# SMD_VR_2023-05-26.net
KiCad netlist of a schematic drawn in Altium Designer
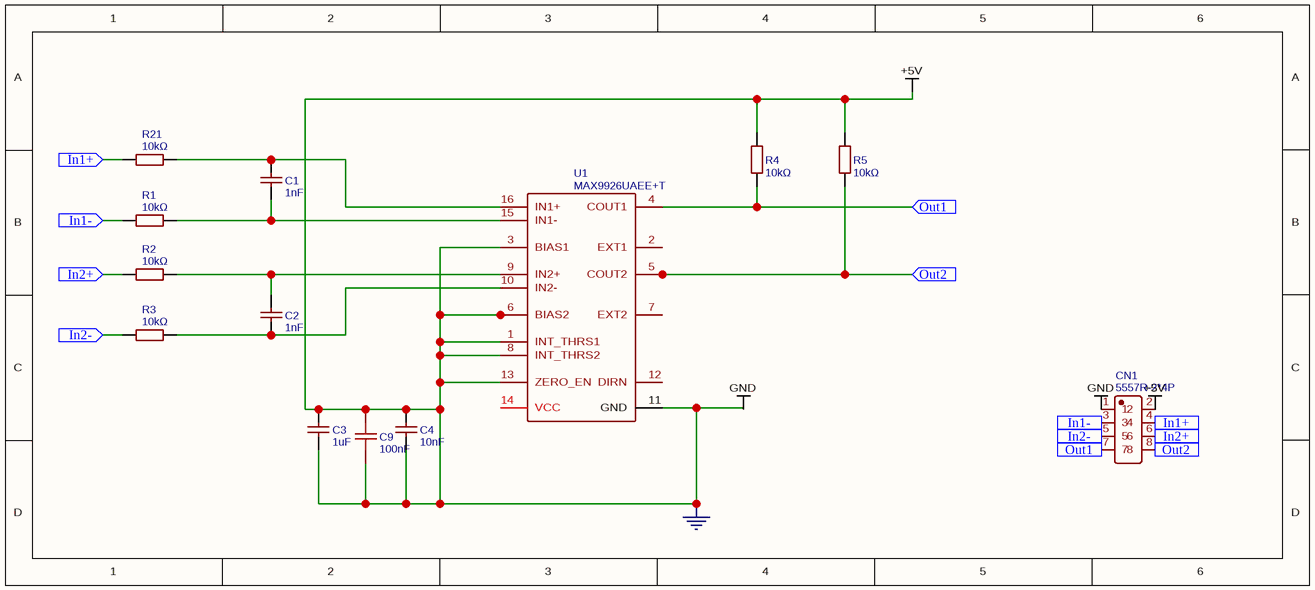
[diagram p0: SMD VR_2023-05-26.schdoc]

(export (version "E")
  (design (tool "Eeschema 10.0.6"))
  (components
    (comp (ref "C1")
      (value "1nF")
      (fields
        (field (name "BOM_MANUFACTURER PART") "CL10B102KB8NNNC")
        (field (name "BOM_SUPPLIER PART") "C1588")
      )
      (libsource (lib "altium-import") (part "root_1_1nF_"))
    )
    (comp (ref "C2")
      (value "1nF")
      (fields
        (field (name "BOM_MANUFACTURER PART") "CL10B102KB8NNNC")
        (field (name "BOM_SUPPLIER PART") "C1588")
      )
      (libsource (lib "altium-import") (part "root_1_1nF_"))
    )
    (comp (ref "C3")
      (value "1uF")
      (fields
        (field (name "BOM_MANUFACTURER PART") "CL10A105KB8NNNC")
        (field (name "BOM_SUPPLIER PART") "C15849")
      )
      (libsource (lib "altium-import") (part "root_1_1uF_"))
    )
    (comp (ref "C4")
      (value "10nF")
      (fields
        (field (name "BOM_MANUFACTURER PART") "CL05B103KB5NNNC")
        (field (name "BOM_SUPPLIER PART") "C15195")
      )
      (libsource (lib "altium-import") (part "root_1_10nF_"))
    )
    (comp (ref "C9")
      (value "100nF")
      (fields
        (field (name "BOM_MANUFACTURER PART") "CC0603KRX7R9BB104")
        (field (name "BOM_SUPPLIER PART") "C14663")
      )
      (libsource (lib "altium-import") (part "root_1_100nF_"))
    )
    (comp (ref "CN1")
      (value "5557R-2*4P")
      (fields (field (name "BOM_SUPPLIER PART") "C477838") (field (name "CONTRIBUTOR") "LCSC"))
      (libsource (lib "altium-import") (part "root_0_5557R-2*4P_"))
    )
    (comp (ref "R1")
      (value "10kΩ")
      (fields
        (field (name "BOM_MANUFACTURER PART") "0402WGF1002TCE")
        (field (name "BOM_SUPPLIER PART") "C25744")
      )
      (libsource (lib "altium-import") (part "root_2_10kΩ_"))
    )
    (comp (ref "R2")
      (value "10kΩ")
      (fields
        (field (name "BOM_MANUFACTURER PART") "0402WGF1002TCE")
        (field (name "BOM_SUPPLIER PART") "C25744")
      )
      (libsource (lib "altium-import") (part "root_2_10kΩ_"))
    )
    (comp (ref "R3")
      (value "10kΩ")
      (fields
        (field (name "BOM_MANUFACTURER PART") "0402WGF1002TCE")
        (field (name "BOM_SUPPLIER PART") "C25744")
      )
      (libsource (lib "altium-import") (part "root_2_10kΩ_"))
    )
    (comp (ref "R4")
      (value "10kΩ")
      (fields
        (field (name "BOM_MANUFACTURER PART") "0402WGF1002TCE")
        (field (name "BOM_SUPPLIER PART") "C25744")
      )
      (libsource (lib "altium-import") (part "root_3_10kΩ_"))
    )
    (comp (ref "R5")
      (value "10kΩ")
      (fields
        (field (name "BOM_MANUFACTURER PART") "0402WGF1002TCE")
        (field (name "BOM_SUPPLIER PART") "C25744")
      )
      (libsource (lib "altium-import") (part "root_3_10kΩ_"))
    )
    (comp (ref "R21")
      (value "10kΩ")
      (fields
        (field (name "BOM_MANUFACTURER PART") "0402WGF1002TCE")
        (field (name "BOM_SUPPLIER PART") "C25744")
      )
      (libsource (lib "altium-import") (part "root_2_10kΩ_"))
    )
    (comp (ref "U1")
      (value "MAX9926UAEE+T")
      (fields (field (name "BOM_MANUFACTURER PART") "?"))
      (libsource (lib "altium-import") (part "root_0_MAX9926UAEE+T_"))
    )
  )
  (nets
    (net (code "1") (name "+5V") (class "Default")
      (node (ref "C3") (pin "1") (pinfunction "1_1") (pintype "passive"))
      (node (ref "C3") (pin "2") (pinfunction "2_2") (pintype "passive"))
      (node (ref "C4") (pin "1") (pinfunction "1_1") (pintype "passive"))
      (node (ref "C4") (pin "2") (pinfunction "2_2") (pintype "passive"))
      (node (ref "C9") (pin "1") (pinfunction "1_1") (pintype "passive"))
      (node (ref "C9") (pin "2") (pinfunction "2_2") (pintype "passive"))
      (node (ref "CN1") (pin "1") (pinfunction "1_1") (pintype "passive"))
      (node (ref "CN1") (pin "2") (pinfunction "2_2") (pintype "passive"))
      (node (ref "R4") (pin "1") (pinfunction "1_1") (pintype "passive"))
      (node (ref "R5") (pin "1") (pinfunction "1_1") (pintype "passive"))
      (node (ref "U1") (pin "1") (pinfunction "INT_THRS1_1") (pintype "passive"))
      (node (ref "U1") (pin "11") (pinfunction "GND_11") (pintype "passive"))
      (node (ref "U1") (pin "13") (pinfunction "ZERO_EN_13") (pintype "passive"))
      (node (ref "U1") (pin "3") (pinfunction "BIAS1_3") (pintype "passive"))
      (node (ref "U1") (pin "6") (pinfunction "BIAS2_6") (pintype "passive"))
      (node (ref "U1") (pin "8") (pinfunction "INT_THRS2_8") (pintype "passive"))
    )
    (net (code "2") (name "/In1+") (class "Default")
      (node (ref "CN1") (pin "4") (pinfunction "4_4") (pintype "passive"))
      (node (ref "R21") (pin "2") (pinfunction "2_2") (pintype "passive"))
    )
    (net (code "3") (name "/In1-") (class "Default")
      (node (ref "CN1") (pin "3") (pinfunction "3_3") (pintype "passive"))
      (node (ref "R1") (pin "2") (pinfunction "2_2") (pintype "passive"))
    )
    (net (code "4") (name "/In2+") (class "Default")
      (node (ref "CN1") (pin "6") (pinfunction "6_6") (pintype "passive"))
      (node (ref "R2") (pin "2") (pinfunction "2_2") (pintype "passive"))
    )
    (net (code "5") (name "/In2-") (class "Default")
      (node (ref "CN1") (pin "5") (pinfunction "5_5") (pintype "passive"))
      (node (ref "R3") (pin "2") (pinfunction "2_2") (pintype "passive"))
    )
    (net (code "6") (name "/Out1") (class "Default")
      (node (ref "CN1") (pin "7") (pinfunction "7_7") (pintype "passive"))
      (node (ref "R4") (pin "2") (pinfunction "2_2") (pintype "passive"))
      (node (ref "U1") (pin "4") (pinfunction "COUT1_4") (pintype "passive"))
    )
    (net (code "7") (name "/Out2") (class "Default")
      (node (ref "CN1") (pin "8") (pinfunction "8_8") (pintype "passive"))
      (node (ref "R5") (pin "2") (pinfunction "2_2") (pintype "passive"))
      (node (ref "U1") (pin "5") (pinfunction "COUT2_5") (pintype "passive"))
    )
    (net (code "8") (name "Net-(U1-IN1+)") (class "Default")
      (node (ref "C1") (pin "2") (pinfunction "2_2") (pintype "passive"))
      (node (ref "R21") (pin "1") (pinfunction "1_1") (pintype "passive"))
      (node (ref "U1") (pin "16") (pinfunction "IN1+_16") (pintype "passive"))
    )
    (net (code "9") (name "Net-(U1-IN1-)") (class "Default")
      (node (ref "C1") (pin "1") (pinfunction "1_1") (pintype "passive"))
      (node (ref "R1") (pin "1") (pinfunction "1_1") (pintype "passive"))
      (node (ref "U1") (pin "15") (pinfunction "IN1-_15") (pintype "passive"))
    )
    (net (code "10") (name "Net-(U1-IN2+)") (class "Default")
      (node (ref "C2") (pin "2") (pinfunction "2_2") (pintype "passive"))
      (node (ref "R2") (pin "1") (pinfunction "1_1") (pintype "passive"))
      (node (ref "U1") (pin "9") (pinfunction "IN2+_9") (pintype "passive"))
    )
    (net (code "11") (name "Net-(U1-IN2-)") (class "Default")
      (node (ref "C2") (pin "1") (pinfunction "1_1") (pintype "passive"))
      (node (ref "R3") (pin "1") (pinfunction "1_1") (pintype "passive"))
      (node (ref "U1") (pin "10") (pinfunction "IN2-_10") (pintype "passive"))
    )
    (net (code "12") (name "unconnected-(U1-DIRN-Pad12)") (class "Default")
      (node (ref "U1") (pin "12") (pinfunction "DIRN_12") (pintype "passive"))
    )
    (net (code "13") (name "unconnected-(U1-EXT1-Pad2)") (class "Default")
      (node (ref "U1") (pin "2") (pinfunction "EXT1_2") (pintype "passive"))
    )
    (net (code "14") (name "unconnected-(U1-EXT2-Pad7)") (class "Default")
      (node (ref "U1") (pin "7") (pinfunction "EXT2_7") (pintype "passive"))
    )
    (net (code "15") (name "unconnected-(U1-VCC-Pad14)") (class "Default")
      (node (ref "U1") (pin "14") (pinfunction "VCC_14") (pintype "passive"))
    )
  )
)
